# RS-core-schematic.net
KiCad netlist of a schematic drawn in EasyEDA
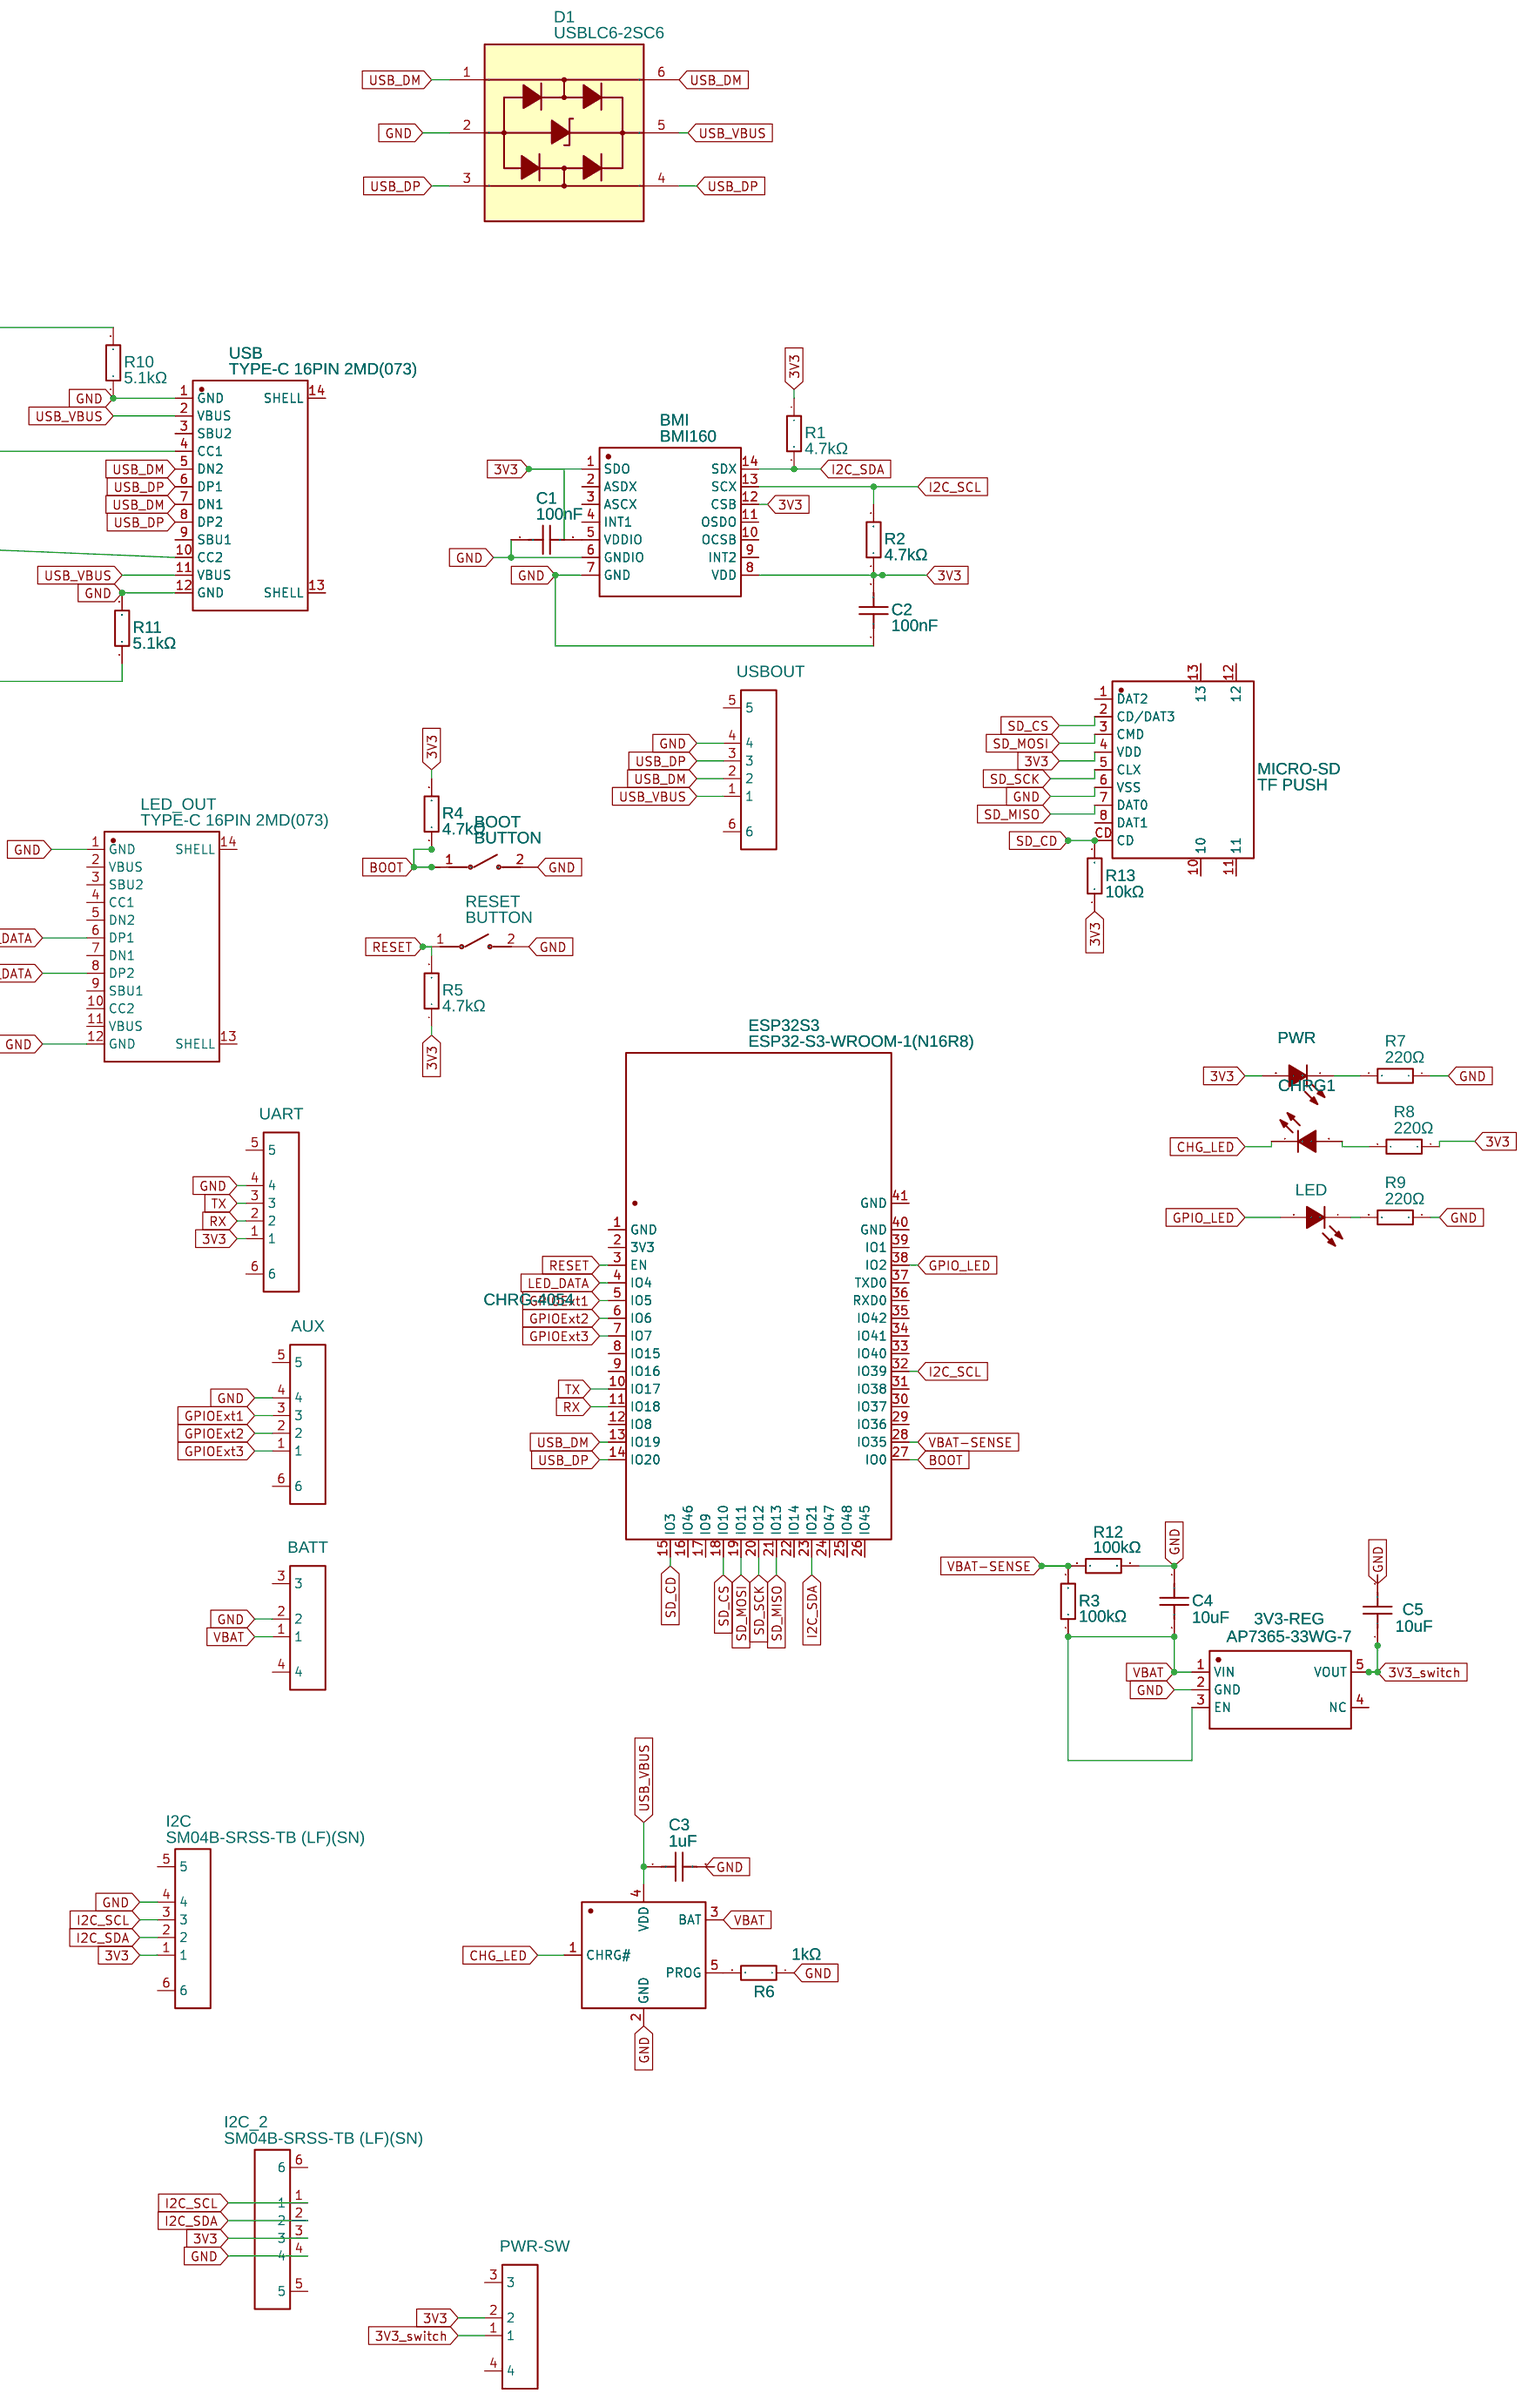
[diagram p0: schematic sheet]

(export (version "E")
  (design (tool "Eeschema 10.0.6"))
  (components
    (comp (ref "3V3-REG")
      (value "AP7365-33WG-7")
      (fields (field (name "Manufacturer") "DIODES(美台)"))
      (libsource (lib "") (part "AP7365-33WG-7"))
    )
    (comp (ref "AUX")
      (value "SM04B-SRSS-TB (LF)(SN)")
      (fields (field (name "Manufacturer Part") "SM04B-SRSS-TB(LF)(SN)") (field (name "Manufacturer") "JST"))
      (libsource (lib "") (part "SM04B-SRSS-TB (LF)(SN)_4"))
    )
    (comp (ref "BATT")
      (value "SM02B-SRSS-TB (LF)(SN)")
      (fields (field (name "Manufacturer Part") "SM02B-SRSS-TB(LF)(SN)") (field (name "Manufacturer") "JST"))
      (libsource (lib "") (part "SM02B-SRSS-TB (LF)(SN)_1"))
    )
    (comp (ref "BMI")
      (value "BMI160")
      (fields (field (name "Manufacturer") "Bosch(博世)"))
      (libsource (lib "") (part "BMI160"))
    )
    (comp (ref "BOOT") (value "BUTTON") (libsource (lib "") (part "BUTTON")))
    (comp (ref "C1")
      (value "100nF")
      (fields
        (field (name "Manufacturer Part") "GCQ1555C1HR10WB01D")
        (field (name "Manufacturer") "muRata(村田)")
      )
      (libsource (lib "") (part "GCQ1555C1HR10WB01D_3"))
    )
    (comp (ref "C2")
      (value "100nF")
      (fields
        (field (name "Manufacturer Part") "GCQ1555C1HR10WB01D")
        (field (name "Manufacturer") "muRata(村田)")
      )
      (libsource (lib "") (part "GCQ1555C1HR10WB01D"))
    )
    (comp (ref "C3")
      (value "1uF")
      (fields
        (field (name "Manufacturer Part") "GCQ1555C1HR10WB01D")
        (field (name "Manufacturer") "muRata(村田)")
      )
      (libsource (lib "") (part "GCQ1555C1HR10WB01D_1"))
    )
    (comp (ref "C4")
      (value "10uF")
      (fields
        (field (name "Manufacturer Part") "GCQ1555C1HR10WB01D")
        (field (name "Manufacturer") "muRata(村田)")
      )
      (libsource (lib "") (part "GCQ1555C1HR10WB01D_2"))
    )
    (comp (ref "C5")
      (value "10uF")
      (fields
        (field (name "Manufacturer Part") "GCQ1555C1HR10WB01D")
        (field (name "Manufacturer") "muRata(村田)")
      )
      (libsource (lib "") (part "GCQ1555C1HR10WB01D"))
    )
    (comp (ref "CHRG-4054")
      (value "Chrg-4054")
      (fields (field (name "Manufacturer Part") "TP4054(LX)") (field (name "Manufacturer") "LX(灵星芯微)"))
      (libsource (lib "") (part "TP4054(LX)"))
    )
    (comp (ref "CHRG1")
      (value "19-217/BHC-ZL1M2RY/3T")
      (fields (field (name "Manufacturer") "EVERLIGHT(亿光)"))
      (libsource (lib "") (part "19-217/BHC-ZL1M2RY/3T"))
    )
    (comp (ref "D1")
      (value "USBLC6-2SC6")
      (fields (field (name "Manufacturer") "ST(意法半导体)"))
      (libsource (lib "") (part "USBLC6-2SC6"))
    )
    (comp (ref "ESP32S3")
      (value "ESP32-S3-WROOM-1(N16R8)")
      (fields
        (field (name "Manufacturer Part") "ESP32-S3-WROOM-1-N16R8")
        (field (name "Manufacturer") "ESPRESSIF(乐鑫)")
      )
      (libsource (lib "") (part "ESP32-S3-WROOM-1(N16R8)"))
    )
    (comp (ref "I2C")
      (value "SM04B-SRSS-TB (LF)(SN)")
      (fields (field (name "Manufacturer Part") "SM04B-SRSS-TB(LF)(SN)") (field (name "Manufacturer") "JST"))
      (libsource (lib "") (part "SM04B-SRSS-TB (LF)(SN)_1"))
    )
    (comp (ref "I2C_2")
      (value "SM04B-SRSS-TB (LF)(SN)")
      (fields (field (name "Manufacturer Part") "SM04B-SRSS-TB(LF)(SN)") (field (name "Manufacturer") "JST"))
      (libsource (lib "") (part "SM04B-SRSS-TB (LF)(SN)_3"))
    )
    (comp (ref "LED")
      (value "19-217/BHC-ZL1M2RY/3T")
      (fields (field (name "Manufacturer") "EVERLIGHT(亿光)"))
      (libsource (lib "") (part "19-217/BHC-ZL1M2RY/3T_2"))
    )
    (comp (ref "LED_OUT")
      (value "TYPE-C 16PIN 2MD(073)")
      (fields (field (name "Manufacturer") "SHOU HAN(首韩)"))
      (libsource (lib "") (part "TYPE-C 16PIN 2MD(073)"))
    )
    (comp (ref "MICRO-SD")
      (value "TF PUSH")
      (fields (field (name "Manufacturer") "SHOU HAN(首韩)"))
      (libsource (lib "") (part "TF PUSH"))
    )
    (comp (ref "PWR")
      (value "19-217/BHC-ZL1M2RY/3T")
      (fields (field (name "Manufacturer") "EVERLIGHT(亿光)"))
      (libsource (lib "") (part "19-217/BHC-ZL1M2RY/3T_1"))
    )
    (comp (ref "PWR-SW")
      (value "SM02B-SRSS-TB (LF)(SN)")
      (fields (field (name "Manufacturer Part") "SM02B-SRSS-TB(LF)(SN)") (field (name "Manufacturer") "JST"))
      (libsource (lib "") (part "SM02B-SRSS-TB (LF)(SN)"))
    )
    (comp (ref "R1")
      (value "4.7kΩ")
      (fields (field (name "Manufacturer Part") "RMC04024K7FN") (field (name "Manufacturer") "Tyohm(幸亚电阻)"))
      (libsource (lib "") (part "RMC04024.7K1%N_1"))
    )
    (comp (ref "R2")
      (value "4.7kΩ")
      (fields (field (name "Manufacturer Part") "RMC04024K7FN") (field (name "Manufacturer") "Tyohm(幸亚电阻)"))
      (libsource (lib "") (part "RMC04024.7K1%N"))
    )
    (comp (ref "R3")
      (value "100kΩ")
      (fields
        (field (name "Manufacturer Part") "0603WAF1003T5E")
        (field (name "Manufacturer") "UNI-ROYAL(厚声)")
      )
      (libsource (lib "") (part "0603WAF1003T5E_1"))
    )
    (comp (ref "R4")
      (value "4.7kΩ")
      (fields (field (name "Manufacturer Part") "CR254701F") (field (name "Manufacturer") "Meritek"))
      (libsource (lib "") (part "CR254701F"))
    )
    (comp (ref "R5")
      (value "4.7kΩ")
      (fields (field (name "Manufacturer Part") "CR254701F") (field (name "Manufacturer") "Meritek"))
      (libsource (lib "") (part "CR254701F"))
    )
    (comp (ref "R6")
      (value "1kΩ")
      (fields (field (name "Manufacturer Part") "CR254701F") (field (name "Manufacturer") "Meritek"))
      (libsource (lib "") (part "CR254701F_1"))
    )
    (comp (ref "R7")
      (value "220Ω")
      (fields (field (name "Manufacturer Part") "CR254701F") (field (name "Manufacturer") "Meritek"))
      (libsource (lib "") (part "CR254701F_1"))
    )
    (comp (ref "R8")
      (value "220Ω")
      (fields (field (name "Manufacturer Part") "CR254701F") (field (name "Manufacturer") "Meritek"))
      (libsource (lib "") (part "CR254701F_1"))
    )
    (comp (ref "R9")
      (value "220Ω")
      (fields (field (name "Manufacturer Part") "CR254701F") (field (name "Manufacturer") "Meritek"))
      (libsource (lib "") (part "CR254701F_1"))
    )
    (comp (ref "R10")
      (value "5.1kΩ")
      (fields (field (name "Manufacturer Part") "CR254701F") (field (name "Manufacturer") "Meritek"))
      (libsource (lib "") (part "CR254701F"))
    )
    (comp (ref "R11")
      (value "5.1kΩ")
      (fields (field (name "Manufacturer Part") "CR254701F") (field (name "Manufacturer") "Meritek"))
      (libsource (lib "") (part "CR254701F"))
    )
    (comp (ref "R12")
      (value "100kΩ")
      (fields
        (field (name "Manufacturer Part") "0603WAF1003T5E")
        (field (name "Manufacturer") "UNI-ROYAL(厚声)")
      )
      (libsource (lib "") (part "0603WAF1003T5E"))
    )
    (comp (ref "R13")
      (value "10kΩ")
      (fields
        (field (name "Manufacturer Part") "0603WAF1002T5E")
        (field (name "Manufacturer") "UNI-ROYAL(厚声)")
      )
      (libsource (lib "") (part "0603WAF1002T5E"))
    )
    (comp (ref "RESET") (value "BUTTON") (libsource (lib "") (part "BUTTON_1")))
    (comp (ref "UART")
      (value "SM04B-SRSS-TB (LF)(SN)")
      (fields (field (name "Manufacturer Part") "SM04B-SRSS-TB(LF)(SN)") (field (name "Manufacturer") "JST"))
      (libsource (lib "") (part "SM04B-SRSS-TB (LF)(SN)_2"))
    )
    (comp (ref "USB")
      (value "TYPE-C 16PIN 2MD(073)")
      (fields (field (name "Manufacturer") "SHOU HAN(首韩)"))
      (libsource (lib "") (part "TYPE-C 16PIN 2MD(073)_1"))
    )
    (comp (ref "USBOUT")
      (value "SM04B-SRSS-TB (LF)(SN)")
      (fields (field (name "Manufacturer Part") "SM04B-SRSS-TB(LF)(SN)") (field (name "Manufacturer") "JST"))
      (libsource (lib "") (part "SM04B-SRSS-TB (LF)(SN)"))
    )
  )
  (nets
    (net (code "1") (name "3V3") (class "Default")
      (node (ref "BMI") (pin "1") (pinfunction "SDO_1") (pintype "unspecified"))
      (node (ref "BMI") (pin "12") (pinfunction "CSB_12") (pintype "unspecified"))
      (node (ref "BMI") (pin "8") (pinfunction "VDD_8") (pintype "unspecified"))
      (node (ref "C2") (pin "2") (pinfunction "2_2") (pintype "unspecified"))
      (node (ref "I2C") (pin "1") (pinfunction "1_1") (pintype "unspecified"))
      (node (ref "I2C_2") (pin "3") (pinfunction "3_3") (pintype "unspecified"))
      (node (ref "MICRO-SD") (pin "4") (pinfunction "VDD_4") (pintype "unspecified"))
      (node (ref "PWR") (pin "2") (pinfunction "A_2") (pintype "input"))
      (node (ref "PWR-SW") (pin "2") (pinfunction "2_2") (pintype "unspecified"))
      (node (ref "R1") (pin "1") (pinfunction "1_1") (pintype "unspecified"))
      (node (ref "R13") (pin "1") (pinfunction "1_1") (pintype "input"))
      (node (ref "R2") (pin "1") (pinfunction "1_1") (pintype "unspecified"))
      (node (ref "R4") (pin "2") (pinfunction "2_2") (pintype "unspecified"))
      (node (ref "R5") (pin "1") (pinfunction "1_1") (pintype "unspecified"))
      (node (ref "R8") (pin "1") (pinfunction "1_1") (pintype "unspecified"))
      (node (ref "UART") (pin "1") (pinfunction "1_1") (pintype "unspecified"))
    )
    (net (code "2") (name "3V3_switch") (class "Default")
      (node (ref "3V3-REG") (pin "5") (pinfunction "VOUT_5") (pintype "unspecified"))
      (node (ref "C5") (pin "1") (pinfunction "1_1") (pintype "unspecified"))
      (node (ref "PWR-SW") (pin "1") (pinfunction "1_1") (pintype "unspecified"))
    )
    (net (code "3") (name "BOOT") (class "Default")
      (node (ref "BOOT") (pin "1") (pinfunction "1_1") (pintype "unspecified"))
      (node (ref "ESP32S3") (pin "27") (pinfunction "IO0_27") (pintype "unspecified"))
      (node (ref "R4") (pin "1") (pinfunction "1_1") (pintype "unspecified"))
    )
    (net (code "4") (name "CHG_LED") (class "Default")
      (node (ref "CHRG-4054") (pin "1") (pinfunction "CHRG#_1") (pintype "unspecified"))
      (node (ref "CHRG1") (pin "1") (pinfunction "C_1") (pintype "input"))
    )
    (net (code "5") (name "GND") (class "Default")
      (node (ref "3V3-REG") (pin "2") (pinfunction "GND_2") (pintype "unspecified"))
      (node (ref "AUX") (pin "4") (pinfunction "4_4") (pintype "unspecified"))
      (node (ref "BATT") (pin "2") (pinfunction "2_2") (pintype "unspecified"))
      (node (ref "BMI") (pin "6") (pinfunction "GNDIO_6") (pintype "unspecified"))
      (node (ref "BMI") (pin "7") (pinfunction "GND_7") (pintype "unspecified"))
      (node (ref "BOOT") (pin "2") (pinfunction "2_2") (pintype "unspecified"))
      (node (ref "C1") (pin "2") (pinfunction "2_2") (pintype "unspecified"))
      (node (ref "C2") (pin "1") (pinfunction "1_1") (pintype "unspecified"))
      (node (ref "C3") (pin "2") (pinfunction "2_2") (pintype "unspecified"))
      (node (ref "C4") (pin "1") (pinfunction "1_1") (pintype "unspecified"))
      (node (ref "C5") (pin "2") (pinfunction "2_2") (pintype "unspecified"))
      (node (ref "CHRG-4054") (pin "2") (pinfunction "GND_2") (pintype "unspecified"))
      (node (ref "D1") (pin "2") (pinfunction "2_2") (pintype "input"))
      (node (ref "I2C") (pin "4") (pinfunction "4_4") (pintype "unspecified"))
      (node (ref "I2C_2") (pin "4") (pinfunction "4_4") (pintype "unspecified"))
      (node (ref "LED_OUT") (pin "1") (pinfunction "GND_1") (pintype "unspecified"))
      (node (ref "LED_OUT") (pin "12") (pinfunction "GND_12") (pintype "unspecified"))
      (node (ref "MICRO-SD") (pin "6") (pinfunction "VSS_6") (pintype "unspecified"))
      (node (ref "R10") (pin "1") (pinfunction "1_1") (pintype "unspecified"))
      (node (ref "R11") (pin "2") (pinfunction "2_2") (pintype "unspecified"))
      (node (ref "R12") (pin "2") (pinfunction "2_2") (pintype "input"))
      (node (ref "R6") (pin "1") (pinfunction "1_1") (pintype "unspecified"))
      (node (ref "R7") (pin "1") (pinfunction "1_1") (pintype "unspecified"))
      (node (ref "R9") (pin "1") (pinfunction "1_1") (pintype "unspecified"))
      (node (ref "RESET") (pin "2") (pinfunction "2_2") (pintype "unspecified"))
      (node (ref "UART") (pin "4") (pinfunction "4_4") (pintype "unspecified"))
      (node (ref "USB") (pin "1") (pinfunction "GND_1") (pintype "unspecified"))
      (node (ref "USB") (pin "12") (pinfunction "GND_12") (pintype "unspecified"))
      (node (ref "USBOUT") (pin "4") (pinfunction "4_4") (pintype "unspecified"))
    )
    (net (code "6") (name "GPIOExt1") (class "Default")
      (node (ref "AUX") (pin "3") (pinfunction "3_3") (pintype "unspecified"))
      (node (ref "ESP32S3") (pin "5") (pinfunction "IO5_5") (pintype "unspecified"))
    )
    (net (code "7") (name "GPIOExt2") (class "Default")
      (node (ref "AUX") (pin "2") (pinfunction "2_2") (pintype "unspecified"))
      (node (ref "ESP32S3") (pin "6") (pinfunction "IO6_6") (pintype "unspecified"))
    )
    (net (code "8") (name "GPIOExt3") (class "Default")
      (node (ref "AUX") (pin "1") (pinfunction "1_1") (pintype "unspecified"))
      (node (ref "ESP32S3") (pin "7") (pinfunction "IO7_7") (pintype "unspecified"))
    )
    (net (code "9") (name "GPIO_LED") (class "Default")
      (node (ref "ESP32S3") (pin "38") (pinfunction "IO2_38") (pintype "unspecified"))
      (node (ref "LED") (pin "2") (pinfunction "A_2") (pintype "input"))
    )
    (net (code "10") (name "I2C_SCL") (class "Default")
      (node (ref "BMI") (pin "13") (pinfunction "SCX_13") (pintype "unspecified"))
      (node (ref "ESP32S3") (pin "32") (pinfunction "IO39_32") (pintype "unspecified"))
      (node (ref "I2C") (pin "3") (pinfunction "3_3") (pintype "unspecified"))
      (node (ref "I2C_2") (pin "1") (pinfunction "1_1") (pintype "unspecified"))
      (node (ref "R2") (pin "2") (pinfunction "2_2") (pintype "unspecified"))
    )
    (net (code "11") (name "I2C_SDA") (class "Default")
      (node (ref "BMI") (pin "14") (pinfunction "SDX_14") (pintype "unspecified"))
      (node (ref "ESP32S3") (pin "23") (pinfunction "IO21_23") (pintype "unspecified"))
      (node (ref "I2C") (pin "2") (pinfunction "2_2") (pintype "unspecified"))
      (node (ref "I2C_2") (pin "2") (pinfunction "2_2") (pintype "unspecified"))
      (node (ref "R1") (pin "2") (pinfunction "2_2") (pintype "unspecified"))
    )
    (net (code "12") (name "LED_DATA") (class "Default")
      (node (ref "ESP32S3") (pin "4") (pinfunction "IO4_4") (pintype "unspecified"))
      (node (ref "LED_OUT") (pin "6") (pinfunction "DP1_6") (pintype "unspecified"))
      (node (ref "LED_OUT") (pin "8") (pinfunction "DP2_8") (pintype "unspecified"))
    )
    (net (code "13") (name "Net-(BMI-VDDIO)") (class "Default")
      (node (ref "BMI") (pin "5") (pinfunction "VDDIO_5") (pintype "unspecified"))
      (node (ref "C1") (pin "1") (pinfunction "1_1") (pintype "unspecified"))
    )
    (net (code "14") (name "Net-(CHRG-4054-PROG)") (class "Default")
      (node (ref "CHRG-4054") (pin "5") (pinfunction "PROG_5") (pintype "unspecified"))
      (node (ref "R6") (pin "2") (pinfunction "2_2") (pintype "unspecified"))
    )
    (net (code "15") (name "Net-(CHRG1-A)") (class "Default")
      (node (ref "CHRG1") (pin "2") (pinfunction "A_2") (pintype "input"))
      (node (ref "R8") (pin "2") (pinfunction "2_2") (pintype "unspecified"))
    )
    (net (code "16") (name "Net-(LED-C)") (class "Default")
      (node (ref "LED") (pin "1") (pinfunction "C_1") (pintype "input"))
      (node (ref "R9") (pin "2") (pinfunction "2_2") (pintype "unspecified"))
    )
    (net (code "17") (name "Net-(PWR-C)") (class "Default")
      (node (ref "PWR") (pin "1") (pinfunction "C_1") (pintype "input"))
      (node (ref "R7") (pin "2") (pinfunction "2_2") (pintype "unspecified"))
    )
    (net (code "18") (name "Net-(USB-CC1)") (class "Default")
      (node (ref "R10") (pin "2") (pinfunction "2_2") (pintype "unspecified"))
      (node (ref "USB") (pin "4") (pinfunction "CC1_4") (pintype "unspecified"))
    )
    (net (code "19") (name "Net-(USB-CC2)") (class "Default")
      (node (ref "R11") (pin "1") (pinfunction "1_1") (pintype "unspecified"))
      (node (ref "USB") (pin "10") (pinfunction "CC2_10") (pintype "unspecified"))
    )
    (net (code "20") (name "RESET") (class "Default")
      (node (ref "ESP32S3") (pin "3") (pinfunction "EN_3") (pintype "unspecified"))
      (node (ref "R5") (pin "2") (pinfunction "2_2") (pintype "unspecified"))
      (node (ref "RESET") (pin "1") (pinfunction "1_1") (pintype "unspecified"))
    )
    (net (code "21") (name "RX") (class "Default")
      (node (ref "ESP32S3") (pin "11") (pinfunction "IO18_11") (pintype "unspecified"))
      (node (ref "UART") (pin "2") (pinfunction "2_2") (pintype "unspecified"))
    )
    (net (code "22") (name "SD_CD") (class "Default")
      (node (ref "ESP32S3") (pin "15") (pinfunction "IO3_15") (pintype "unspecified"))
      (node (ref "MICRO-SD") (pin "CD") (pinfunction "CD_CD") (pintype "unspecified"))
      (node (ref "R13") (pin "2") (pinfunction "2_2") (pintype "input"))
    )
    (net (code "23") (name "SD_CS") (class "Default")
      (node (ref "ESP32S3") (pin "18") (pinfunction "IO10_18") (pintype "unspecified"))
      (node (ref "MICRO-SD") (pin "2") (pinfunction "CD/DAT3_2") (pintype "unspecified"))
    )
    (net (code "24") (name "SD_MISO") (class "Default")
      (node (ref "ESP32S3") (pin "21") (pinfunction "IO13_21") (pintype "unspecified"))
      (node (ref "MICRO-SD") (pin "7") (pinfunction "DAT0_7") (pintype "unspecified"))
    )
    (net (code "25") (name "SD_MOSI") (class "Default")
      (node (ref "ESP32S3") (pin "19") (pinfunction "IO11_19") (pintype "unspecified"))
      (node (ref "MICRO-SD") (pin "3") (pinfunction "CMD_3") (pintype "unspecified"))
    )
    (net (code "26") (name "SD_SCK") (class "Default")
      (node (ref "ESP32S3") (pin "20") (pinfunction "IO12_20") (pintype "unspecified"))
      (node (ref "MICRO-SD") (pin "5") (pinfunction "CLX_5") (pintype "unspecified"))
    )
    (net (code "27") (name "TX") (class "Default")
      (node (ref "ESP32S3") (pin "10") (pinfunction "IO17_10") (pintype "unspecified"))
      (node (ref "UART") (pin "3") (pinfunction "3_3") (pintype "unspecified"))
    )
    (net (code "28") (name "USB_DM") (class "Default")
      (node (ref "D1") (pin "1") (pinfunction "1_1") (pintype "input"))
      (node (ref "D1") (pin "6") (pinfunction "6_6") (pintype "input"))
      (node (ref "ESP32S3") (pin "13") (pinfunction "IO19_13") (pintype "unspecified"))
      (node (ref "USB") (pin "5") (pinfunction "DN2_5") (pintype "unspecified"))
      (node (ref "USB") (pin "7") (pinfunction "DN1_7") (pintype "unspecified"))
      (node (ref "USBOUT") (pin "2") (pinfunction "2_2") (pintype "unspecified"))
    )
    (net (code "29") (name "USB_DP") (class "Default")
      (node (ref "D1") (pin "3") (pinfunction "3_3") (pintype "input"))
      (node (ref "D1") (pin "4") (pinfunction "4_4") (pintype "input"))
      (node (ref "ESP32S3") (pin "14") (pinfunction "IO20_14") (pintype "unspecified"))
      (node (ref "USB") (pin "6") (pinfunction "DP1_6") (pintype "unspecified"))
      (node (ref "USB") (pin "8") (pinfunction "DP2_8") (pintype "unspecified"))
      (node (ref "USBOUT") (pin "3") (pinfunction "3_3") (pintype "unspecified"))
    )
    (net (code "30") (name "USB_VBUS") (class "Default")
      (node (ref "C3") (pin "1") (pinfunction "1_1") (pintype "unspecified"))
      (node (ref "CHRG-4054") (pin "4") (pinfunction "VDD_4") (pintype "unspecified"))
      (node (ref "D1") (pin "5") (pinfunction "5_5") (pintype "input"))
      (node (ref "USB") (pin "11") (pinfunction "VBUS_11") (pintype "unspecified"))
      (node (ref "USB") (pin "2") (pinfunction "VBUS_2") (pintype "unspecified"))
      (node (ref "USBOUT") (pin "1") (pinfunction "1_1") (pintype "unspecified"))
    )
    (net (code "31") (name "VBAT") (class "Default")
      (node (ref "3V3-REG") (pin "1") (pinfunction "VIN_1") (pintype "unspecified"))
      (node (ref "3V3-REG") (pin "3") (pinfunction "EN_3") (pintype "unspecified"))
      (node (ref "BATT") (pin "1") (pinfunction "1_1") (pintype "unspecified"))
      (node (ref "C4") (pin "2") (pinfunction "2_2") (pintype "unspecified"))
      (node (ref "CHRG-4054") (pin "3") (pinfunction "BAT_3") (pintype "unspecified"))
      (node (ref "R3") (pin "1") (pinfunction "1_1") (pintype "input"))
    )
    (net (code "32") (name "VBAT-SENSE") (class "Default")
      (node (ref "ESP32S3") (pin "28") (pinfunction "IO35_28") (pintype "unspecified"))
      (node (ref "R12") (pin "1") (pinfunction "1_1") (pintype "input"))
      (node (ref "R3") (pin "2") (pinfunction "2_2") (pintype "input"))
    )
    (net (code "33") (name "unconnected-(3V3-REG-NC-Pad4)") (class "Default")
      (node (ref "3V3-REG") (pin "4") (pinfunction "NC_4") (pintype "unspecified"))
    )
    (net (code "34") (name "unconnected-(AUX-Pad5)") (class "Default")
      (node (ref "AUX") (pin "5") (pinfunction "5_5") (pintype "unspecified"))
    )
    (net (code "35") (name "unconnected-(AUX-Pad6)") (class "Default")
      (node (ref "AUX") (pin "6") (pinfunction "6_6") (pintype "unspecified"))
    )
    (net (code "36") (name "unconnected-(BATT-Pad3)") (class "Default")
      (node (ref "BATT") (pin "3") (pinfunction "3_3") (pintype "unspecified"))
    )
    (net (code "37") (name "unconnected-(BATT-Pad4)") (class "Default")
      (node (ref "BATT") (pin "4") (pinfunction "4_4") (pintype "unspecified"))
    )
    (net (code "38") (name "unconnected-(BMI-ASCX-Pad3)") (class "Default")
      (node (ref "BMI") (pin "3") (pinfunction "ASCX_3") (pintype "unspecified"))
    )
    (net (code "39") (name "unconnected-(BMI-ASDX-Pad2)") (class "Default")
      (node (ref "BMI") (pin "2") (pinfunction "ASDX_2") (pintype "unspecified"))
    )
    (net (code "40") (name "unconnected-(BMI-INT1-Pad4)") (class "Default")
      (node (ref "BMI") (pin "4") (pinfunction "INT1_4") (pintype "unspecified"))
    )
    (net (code "41") (name "unconnected-(BMI-INT2-Pad9)") (class "Default")
      (node (ref "BMI") (pin "9") (pinfunction "INT2_9") (pintype "unspecified"))
    )
    (net (code "42") (name "unconnected-(BMI-OCSB-Pad10)") (class "Default")
      (node (ref "BMI") (pin "10") (pinfunction "OCSB_10") (pintype "unspecified"))
    )
    (net (code "43") (name "unconnected-(BMI-OSDO-Pad11)") (class "Default")
      (node (ref "BMI") (pin "11") (pinfunction "OSDO_11") (pintype "unspecified"))
    )
    (net (code "44") (name "unconnected-(ESP32S3-3V3-Pad2)") (class "Default")
      (node (ref "ESP32S3") (pin "2") (pinfunction "3V3_2") (pintype "unspecified"))
    )
    (net (code "45") (name "unconnected-(ESP32S3-GND-Pad1)") (class "Default")
      (node (ref "ESP32S3") (pin "1") (pinfunction "GND_1") (pintype "unspecified"))
    )
    (net (code "46") (name "unconnected-(ESP32S3-GND-Pad40)") (class "Default")
      (node (ref "ESP32S3") (pin "40") (pinfunction "GND_40") (pintype "unspecified"))
    )
    (net (code "47") (name "unconnected-(ESP32S3-GND-Pad41)") (class "Default")
      (node (ref "ESP32S3") (pin "41") (pinfunction "GND_41") (pintype "unspecified"))
    )
    (net (code "48") (name "unconnected-(ESP32S3-IO1-Pad39)") (class "Default")
      (node (ref "ESP32S3") (pin "39") (pinfunction "IO1_39") (pintype "unspecified"))
    )
    (net (code "49") (name "unconnected-(ESP32S3-IO8-Pad12)") (class "Default")
      (node (ref "ESP32S3") (pin "12") (pinfunction "IO8_12") (pintype "unspecified"))
    )
    (net (code "50") (name "unconnected-(ESP32S3-IO9-Pad17)") (class "Default")
      (node (ref "ESP32S3") (pin "17") (pinfunction "IO9_17") (pintype "unspecified"))
    )
    (net (code "51") (name "unconnected-(ESP32S3-IO14-Pad22)") (class "Default")
      (node (ref "ESP32S3") (pin "22") (pinfunction "IO14_22") (pintype "unspecified"))
    )
    (net (code "52") (name "unconnected-(ESP32S3-IO15-Pad8)") (class "Default")
      (node (ref "ESP32S3") (pin "8") (pinfunction "IO15_8") (pintype "unspecified"))
    )
    (net (code "53") (name "unconnected-(ESP32S3-IO16-Pad9)") (class "Default")
      (node (ref "ESP32S3") (pin "9") (pinfunction "IO16_9") (pintype "unspecified"))
    )
    (net (code "54") (name "unconnected-(ESP32S3-IO36-Pad29)") (class "Default")
      (node (ref "ESP32S3") (pin "29") (pinfunction "IO36_29") (pintype "unspecified"))
    )
    (net (code "55") (name "unconnected-(ESP32S3-IO37-Pad30)") (class "Default")
      (node (ref "ESP32S3") (pin "30") (pinfunction "IO37_30") (pintype "unspecified"))
    )
    (net (code "56") (name "unconnected-(ESP32S3-IO38-Pad31)") (class "Default")
      (node (ref "ESP32S3") (pin "31") (pinfunction "IO38_31") (pintype "unspecified"))
    )
    (net (code "57") (name "unconnected-(ESP32S3-IO40-Pad33)") (class "Default")
      (node (ref "ESP32S3") (pin "33") (pinfunction "IO40_33") (pintype "unspecified"))
    )
    (net (code "58") (name "unconnected-(ESP32S3-IO41-Pad34)") (class "Default")
      (node (ref "ESP32S3") (pin "34") (pinfunction "IO41_34") (pintype "unspecified"))
    )
    (net (code "59") (name "unconnected-(ESP32S3-IO42-Pad35)") (class "Default")
      (node (ref "ESP32S3") (pin "35") (pinfunction "IO42_35") (pintype "unspecified"))
    )
    (net (code "60") (name "unconnected-(ESP32S3-IO45-Pad26)") (class "Default")
      (node (ref "ESP32S3") (pin "26") (pinfunction "IO45_26") (pintype "unspecified"))
    )
    (net (code "61") (name "unconnected-(ESP32S3-IO46-Pad16)") (class "Default")
      (node (ref "ESP32S3") (pin "16") (pinfunction "IO46_16") (pintype "unspecified"))
    )
    (net (code "62") (name "unconnected-(ESP32S3-IO47-Pad24)") (class "Default")
      (node (ref "ESP32S3") (pin "24") (pinfunction "IO47_24") (pintype "unspecified"))
    )
    (net (code "63") (name "unconnected-(ESP32S3-IO48-Pad25)") (class "Default")
      (node (ref "ESP32S3") (pin "25") (pinfunction "IO48_25") (pintype "unspecified"))
    )
    (net (code "64") (name "unconnected-(ESP32S3-RXD0-Pad36)") (class "Default")
      (node (ref "ESP32S3") (pin "36") (pinfunction "RXD0_36") (pintype "unspecified"))
    )
    (net (code "65") (name "unconnected-(ESP32S3-TXD0-Pad37)") (class "Default")
      (node (ref "ESP32S3") (pin "37") (pinfunction "TXD0_37") (pintype "unspecified"))
    )
    (net (code "66") (name "unconnected-(I2C-Pad5)") (class "Default")
      (node (ref "I2C") (pin "5") (pinfunction "5_5") (pintype "unspecified"))
    )
    (net (code "67") (name "unconnected-(I2C-Pad6)") (class "Default")
      (node (ref "I2C") (pin "6") (pinfunction "6_6") (pintype "unspecified"))
    )
    (net (code "68") (name "unconnected-(I2C_2-Pad5)") (class "Default")
      (node (ref "I2C_2") (pin "5") (pinfunction "5_5") (pintype "unspecified"))
    )
    (net (code "69") (name "unconnected-(I2C_2-Pad6)") (class "Default")
      (node (ref "I2C_2") (pin "6") (pinfunction "6_6") (pintype "unspecified"))
    )
    (net (code "70") (name "unconnected-(LED_OUT-CC1-Pad4)") (class "Default")
      (node (ref "LED_OUT") (pin "4") (pinfunction "CC1_4") (pintype "unspecified"))
    )
    (net (code "71") (name "unconnected-(LED_OUT-CC2-Pad10)") (class "Default")
      (node (ref "LED_OUT") (pin "10") (pinfunction "CC2_10") (pintype "unspecified"))
    )
    (net (code "72") (name "unconnected-(LED_OUT-DN1-Pad7)") (class "Default")
      (node (ref "LED_OUT") (pin "7") (pinfunction "DN1_7") (pintype "unspecified"))
    )
    (net (code "73") (name "unconnected-(LED_OUT-DN2-Pad5)") (class "Default")
      (node (ref "LED_OUT") (pin "5") (pinfunction "DN2_5") (pintype "unspecified"))
    )
    (net (code "74") (name "unconnected-(LED_OUT-SBU1-Pad9)") (class "Default")
      (node (ref "LED_OUT") (pin "9") (pinfunction "SBU1_9") (pintype "unspecified"))
    )
    (net (code "75") (name "unconnected-(LED_OUT-SBU2-Pad3)") (class "Default")
      (node (ref "LED_OUT") (pin "3") (pinfunction "SBU2_3") (pintype "unspecified"))
    )
    (net (code "76") (name "unconnected-(LED_OUT-SHELL-Pad13)") (class "Default")
      (node (ref "LED_OUT") (pin "13") (pinfunction "SHELL_13") (pintype "unspecified"))
    )
    (net (code "77") (name "unconnected-(LED_OUT-SHELL-Pad14)") (class "Default")
      (node (ref "LED_OUT") (pin "14") (pinfunction "SHELL_14") (pintype "unspecified"))
    )
    (net (code "78") (name "unconnected-(LED_OUT-VBUS-Pad2)") (class "Default")
      (node (ref "LED_OUT") (pin "2") (pinfunction "VBUS_2") (pintype "unspecified"))
    )
    (net (code "79") (name "unconnected-(LED_OUT-VBUS-Pad11)") (class "Default")
      (node (ref "LED_OUT") (pin "11") (pinfunction "VBUS_11") (pintype "unspecified"))
    )
    (net (code "80") (name "unconnected-(MICRO-SD-DAT1-Pad8)") (class "Default")
      (node (ref "MICRO-SD") (pin "8") (pinfunction "DAT1_8") (pintype "unspecified"))
    )
    (net (code "81") (name "unconnected-(MICRO-SD-DAT2-Pad1)") (class "Default")
      (node (ref "MICRO-SD") (pin "1") (pinfunction "DAT2_1") (pintype "unspecified"))
    )
    (net (code "82") (name "unconnected-(MICRO-SD-Pad10)") (class "Default")
      (node (ref "MICRO-SD") (pin "10") (pinfunction "10_10") (pintype "unspecified"))
    )
    (net (code "83") (name "unconnected-(MICRO-SD-Pad11)") (class "Default")
      (node (ref "MICRO-SD") (pin "11") (pinfunction "11_11") (pintype "unspecified"))
    )
    (net (code "84") (name "unconnected-(MICRO-SD-Pad12)") (class "Default")
      (node (ref "MICRO-SD") (pin "12") (pinfunction "12_12") (pintype "unspecified"))
    )
    (net (code "85") (name "unconnected-(MICRO-SD-Pad13)") (class "Default")
      (node (ref "MICRO-SD") (pin "13") (pinfunction "13_13") (pintype "unspecified"))
    )
    (net (code "86") (name "unconnected-(PWR-SW-Pad3)") (class "Default")
      (node (ref "PWR-SW") (pin "3") (pinfunction "3_3") (pintype "unspecified"))
    )
    (net (code "87") (name "unconnected-(PWR-SW-Pad4)") (class "Default")
      (node (ref "PWR-SW") (pin "4") (pinfunction "4_4") (pintype "unspecified"))
    )
    (net (code "88") (name "unconnected-(UART-Pad5)") (class "Default")
      (node (ref "UART") (pin "5") (pinfunction "5_5") (pintype "unspecified"))
    )
    (net (code "89") (name "unconnected-(UART-Pad6)") (class "Default")
      (node (ref "UART") (pin "6") (pinfunction "6_6") (pintype "unspecified"))
    )
    (net (code "90") (name "unconnected-(USB-SBU1-Pad9)") (class "Default")
      (node (ref "USB") (pin "9") (pinfunction "SBU1_9") (pintype "unspecified"))
    )
    (net (code "91") (name "unconnected-(USB-SBU2-Pad3)") (class "Default")
      (node (ref "USB") (pin "3") (pinfunction "SBU2_3") (pintype "unspecified"))
    )
    (net (code "92") (name "unconnected-(USB-SHELL-Pad13)") (class "Default")
      (node (ref "USB") (pin "13") (pinfunction "SHELL_13") (pintype "unspecified"))
    )
    (net (code "93") (name "unconnected-(USB-SHELL-Pad14)") (class "Default")
      (node (ref "USB") (pin "14") (pinfunction "SHELL_14") (pintype "unspecified"))
    )
    (net (code "94") (name "unconnected-(USBOUT-Pad5)") (class "Default")
      (node (ref "USBOUT") (pin "5") (pinfunction "5_5") (pintype "unspecified"))
    )
    (net (code "95") (name "unconnected-(USBOUT-Pad6)") (class "Default")
      (node (ref "USBOUT") (pin "6") (pinfunction "6_6") (pintype "unspecified"))
    )
  )
)
